# 06_PowerRele_OnOff.net
KiCad netlist of a schematic drawn in Altium Designer
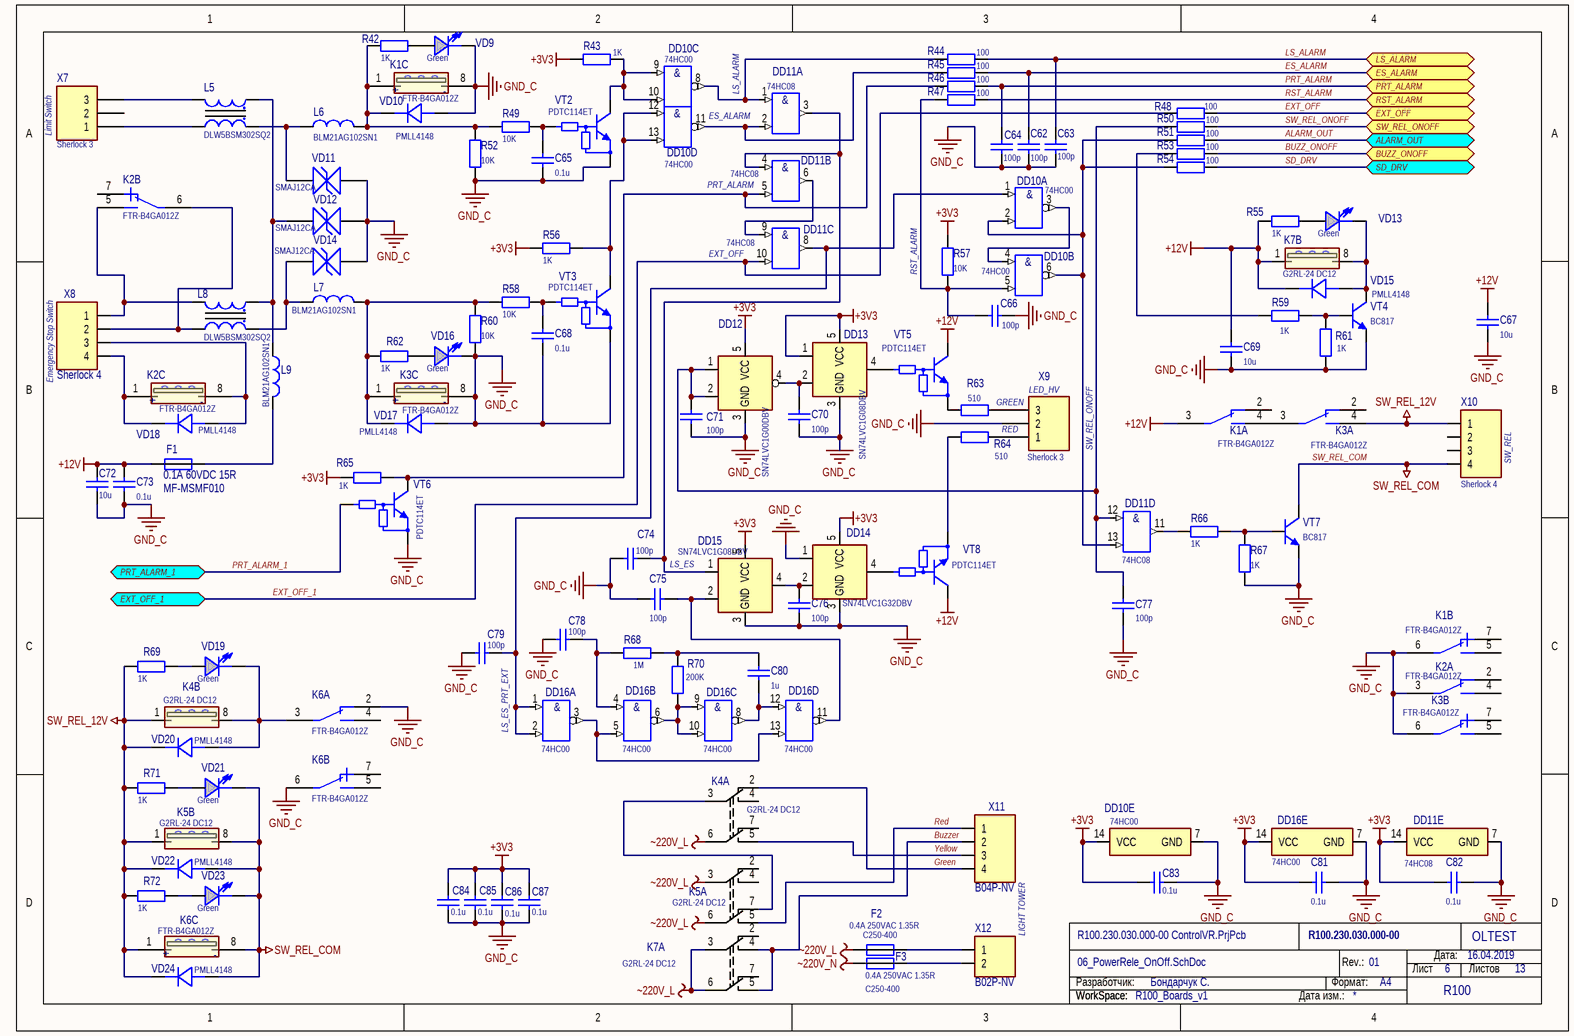
[diagram p0: 06_PowerRele_OnOff.SchDoc]

(export (version "E")
  (design (tool "Eeschema 10.0.6"))
  (components
    (comp (ref "C62")
      (value "100p")
      (footprint "mainLib:SMD_C_0603")
      (description "SMD C 0603 MURATA 100V 5% NP0")
      (fields (field (name "PARTNUMBER") "GRM1885C2A101JA01") (field (name "MANUFACTURER") "MURATA"))
      (libsource (lib "mainRCLib") (part "C0603 100p 100V 5%"))
    )
    (comp (ref "C63")
      (value "100p")
      (footprint "mainLib:SMD_C_0603")
      (description "SMD C 0603 MURATA 100V 5% NP0")
      (fields (field (name "PARTNUMBER") "GRM1885C2A101JA01") (field (name "MANUFACTURER") "MURATA"))
      (libsource (lib "mainRCLib") (part "C0603 100p 100V 5%"))
    )
    (comp (ref "C64")
      (value "100p")
      (footprint "mainLib:SMD_C_0603")
      (description "SMD C 0603 MURATA 100V 5% NP0")
      (fields (field (name "PARTNUMBER") "GRM1885C2A101JA01") (field (name "MANUFACTURER") "MURATA"))
      (libsource (lib "mainRCLib") (part "C0603 100p 100V 5%"))
    )
    (comp (ref "C65")
      (value "0.1u")
      (footprint "mainLib:SMD_C_0603")
      (description "SMD C 0603 MURATA 50V 10% X7R")
      (fields (field (name "PARTNUMBER") "GRM188R71H104K") (field (name "MANUFACTURER") "MURATA"))
      (libsource (lib "mainRCLib") (part "C0603 0.1u 50V 10%"))
    )
    (comp (ref "C66")
      (value "100p")
      (footprint "mainLib:SMD_C_0603")
      (description "SMD C 0603 MURATA 100V 5% NP0")
      (fields (field (name "PARTNUMBER") "GRM1885C2A101JA01") (field (name "MANUFACTURER") "MURATA"))
      (libsource (lib "mainRCLib") (part "C0603 100p 100V 5%"))
    )
    (comp (ref "C67")
      (value "10u")
      (footprint "mainLib:SMD_C_1206")
      (description "SMD C 1206 MURATA 25V 20% X5R")
      (fields (field (name "PARTNUMBER") "GRM31MR61E106M") (field (name "MANUFACTURER") "MURATA"))
      (libsource (lib "mainRCLib") (part "C1206 10u 25V 20%"))
    )
    (comp (ref "C68")
      (value "0.1u")
      (footprint "mainLib:SMD_C_0603")
      (description "SMD C 0603 MURATA 50V 10% X7R")
      (fields (field (name "PARTNUMBER") "GRM188R71H104K") (field (name "MANUFACTURER") "MURATA"))
      (libsource (lib "mainRCLib") (part "C0603 0.1u 50V 10%"))
    )
    (comp (ref "C69")
      (value "10u")
      (footprint "mainLib:SMD_C_1206")
      (description "SMD C 1206 MURATA 25V 20% X5R")
      (fields (field (name "PARTNUMBER") "GRM31MR61E106M") (field (name "MANUFACTURER") "MURATA"))
      (libsource (lib "mainRCLib") (part "C1206 10u 25V 20%"))
    )
    (comp (ref "C70")
      (value "100p")
      (footprint "mainLib:SMD_C_0603")
      (description "SMD C 0603 MURATA 100V 5% NP0")
      (fields (field (name "PARTNUMBER") "GRM1885C2A101JA01") (field (name "MANUFACTURER") "MURATA"))
      (libsource (lib "mainRCLib") (part "C0603 100p 100V 5%"))
    )
    (comp (ref "C71")
      (value "100p")
      (footprint "mainLib:SMD_C_0603")
      (description "SMD C 0603 MURATA 100V 5% NP0")
      (fields (field (name "PARTNUMBER") "GRM1885C2A101JA01") (field (name "MANUFACTURER") "MURATA"))
      (libsource (lib "mainRCLib") (part "C0603 100p 100V 5%"))
    )
    (comp (ref "C72")
      (value "10u")
      (footprint "mainLib:SMD_C_1206")
      (description "SMD C 1206 MURATA 25V 20% X5R")
      (fields (field (name "PARTNUMBER") "GRM31MR61E106M") (field (name "MANUFACTURER") "MURATA"))
      (libsource (lib "mainRCLib") (part "C1206 10u 25V 20%"))
    )
    (comp (ref "C73")
      (value "0.1u")
      (footprint "mainLib:SMD_C_0603")
      (description "SMD C 0603 MURATA 50V 10% X7R")
      (fields (field (name "PARTNUMBER") "GRM188R71H104K") (field (name "MANUFACTURER") "MURATA"))
      (libsource (lib "mainRCLib") (part "C0603 0.1u 50V 10%"))
    )
    (comp (ref "C74")
      (value "100p")
      (footprint "mainLib:SMD_C_0603")
      (description "SMD C 0603 MURATA 100V 5% NP0")
      (fields (field (name "PARTNUMBER") "GRM1885C2A101JA01") (field (name "MANUFACTURER") "MURATA"))
      (libsource (lib "mainRCLib") (part "C0603 100p 100V 5%"))
    )
    (comp (ref "C75")
      (value "100p")
      (footprint "mainLib:SMD_C_0603")
      (description "SMD C 0603 MURATA 100V 5% NP0")
      (fields (field (name "PARTNUMBER") "GRM1885C2A101JA01") (field (name "MANUFACTURER") "MURATA"))
      (libsource (lib "mainRCLib") (part "C0603 100p 100V 5%"))
    )
    (comp (ref "C76")
      (value "100p")
      (footprint "mainLib:SMD_C_0603")
      (description "SMD C 0603 MURATA 100V 5% NP0")
      (fields (field (name "PARTNUMBER") "GRM1885C2A101JA01") (field (name "MANUFACTURER") "MURATA"))
      (libsource (lib "mainRCLib") (part "C0603 100p 100V 5%"))
    )
    (comp (ref "C77")
      (value "100p")
      (footprint "mainLib:SMD_C_0603")
      (description "SMD C 0603 MURATA 100V 5% NP0")
      (fields (field (name "PARTNUMBER") "GRM1885C2A101JA01") (field (name "MANUFACTURER") "MURATA"))
      (libsource (lib "mainRCLib") (part "C0603 100p 100V 5%"))
    )
    (comp (ref "C78")
      (value "100p")
      (footprint "mainLib:SMD_C_0603")
      (description "SMD C 0603 MURATA 100V 5% NP0")
      (fields (field (name "PARTNUMBER") "GRM1885C2A101JA01") (field (name "MANUFACTURER") "MURATA"))
      (libsource (lib "mainRCLib") (part "C0603 100p 100V 5%"))
    )
    (comp (ref "C79")
      (value "100p")
      (footprint "mainLib:SMD_C_0603")
      (description "SMD C 0603 MURATA 100V 5% NP0")
      (fields (field (name "PARTNUMBER") "GRM1885C2A101JA01") (field (name "MANUFACTURER") "MURATA"))
      (libsource (lib "mainRCLib") (part "C0603 100p 100V 5%"))
    )
    (comp (ref "C80")
      (value "1u")
      (footprint "mainLib:SMD_C_0603")
      (description "SMD C 0603 MURATA 25V 10% X7R")
      (fields (field (name "PARTNUMBER") "GRM188R71E105KA12") (field (name "MANUFACTURER") "MURATA"))
      (libsource (lib "mainRCLib") (part "C0603 1uF 25V 10%"))
    )
    (comp (ref "C81")
      (value "0.1u")
      (footprint "mainLib:SMD_C_0603")
      (description "SMD C 0603 MURATA 50V 10% X7R")
      (fields (field (name "PARTNUMBER") "GRM188R71H104K") (field (name "MANUFACTURER") "MURATA"))
      (libsource (lib "mainRCLib") (part "C0603 0.1u 50V 10%"))
    )
    (comp (ref "C82")
      (value "0.1u")
      (footprint "mainLib:SMD_C_0603")
      (description "SMD C 0603 MURATA 50V 10% X7R")
      (fields (field (name "PARTNUMBER") "GRM188R71H104K") (field (name "MANUFACTURER") "MURATA"))
      (libsource (lib "mainRCLib") (part "C0603 0.1u 50V 10%"))
    )
    (comp (ref "C83")
      (value "0.1u")
      (footprint "mainLib:SMD_C_0603")
      (description "SMD C 0603 MURATA 50V 10% X7R")
      (fields (field (name "PARTNUMBER") "GRM188R71H104K") (field (name "MANUFACTURER") "MURATA"))
      (libsource (lib "mainRCLib") (part "C0603 0.1u 50V 10%"))
    )
    (comp (ref "C84")
      (value "0.1u")
      (footprint "mainLib:SMD_C_0603")
      (description "SMD C 0603 MURATA 50V 10% X7R")
      (fields (field (name "PARTNUMBER") "GRM188R71H104K") (field (name "MANUFACTURER") "MURATA"))
      (libsource (lib "mainRCLib") (part "C0603 0.1u 50V 10%"))
    )
    (comp (ref "C85")
      (value "0.1u")
      (footprint "mainLib:SMD_C_0603")
      (description "SMD C 0603 MURATA 50V 10% X7R")
      (fields (field (name "PARTNUMBER") "GRM188R71H104K") (field (name "MANUFACTURER") "MURATA"))
      (libsource (lib "mainRCLib") (part "C0603 0.1u 50V 10%"))
    )
    (comp (ref "C86")
      (value "0.1u")
      (footprint "mainLib:SMD_C_0603")
      (description "SMD C 0603 MURATA 50V 10% X7R")
      (fields (field (name "PARTNUMBER") "GRM188R71H104K") (field (name "MANUFACTURER") "MURATA"))
      (libsource (lib "mainRCLib") (part "C0603 0.1u 50V 10%"))
    )
    (comp (ref "C87")
      (value "0.1u")
      (footprint "mainLib:SMD_C_0603")
      (description "SMD C 0603 MURATA 50V 10% X7R")
      (fields (field (name "PARTNUMBER") "GRM188R71H104K") (field (name "MANUFACTURER") "MURATA"))
      (libsource (lib "mainRCLib") (part "C0603 0.1u 50V 10%"))
    )
    (comp (ref "DD10")
      (value "74HC00")
      (footprint "mainLib:TSSOP14")
      (description "Quad 2-Input Positive-NAND Gates, PW0014A")
      (fields
        (field (name "GENERIC PART NUMBER") "SN74HC00")
        (field (name "MANUFACTURER") "Texas Instruments")
      )
      (libsource (lib "mainLib") (part "74HC00"))
    )
    (comp (ref "DD11")
      (value "74HC08")
      (footprint "mainLib:TSSOP14")
      (description "Quad 2-Input Positive-NAND Gates, PW0014A")
      (fields
        (field (name "GENERIC PART NUMBER") "SN74HC00")
        (field (name "MANUFACTURER") "Texas Instruments")
      )
      (libsource (lib "mainLib") (part "74HC08"))
    )
    (comp (ref "DD12")
      (value "SN74LVC1G00DBV")
      (footprint "mainLib:SOT-23(DBV)")
      (description "2-in NAND")
      (fields (field (name "MANUFACTURER") "Texas Instruments"))
      (libsource (lib "mainLib") (part "SN74LVC1G00DBV"))
    )
    (comp (ref "DD13")
      (value "SN74LVC1G08DBV")
      (footprint "mainLib:SOT-23(DBV)")
      (description "2-in AND")
      (fields (field (name "MANUFACTURER") "Texas Instruments"))
      (libsource (lib "mainLib") (part "SN74LVC1G08DBV"))
    )
    (comp (ref "DD14")
      (value "SN74LVC1G32DBV")
      (footprint "mainLib:SOT-23(DBV)")
      (description "2-in OR")
      (fields (field (name "MANUFACTURER") "Texas Instruments"))
      (libsource (lib "mainLib") (part "SN74LVC1G32DBV"))
    )
    (comp (ref "DD15")
      (value "SN74LVC1G08DBV")
      (footprint "mainLib:SOT-23(DBV)")
      (description "2-in AND")
      (fields (field (name "MANUFACTURER") "Texas Instruments"))
      (libsource (lib "mainLib") (part "SN74LVC1G08DBV"))
    )
    (comp (ref "DD16")
      (value "74HC00")
      (footprint "mainLib:TSSOP14")
      (description "Quad 2-Input Positive-NAND Gates, PW0014A")
      (fields
        (field (name "GENERIC PART NUMBER") "SN74HC00")
        (field (name "MANUFACTURER") "Texas Instruments")
      )
      (libsource (lib "mainLib") (part "74HC00"))
    )
    (comp (ref "F1")
      (value "0.1A 60VDC 15R")
      (footprint "mainLib:MF-MSMF010")
      (description "PTC Resettable Fusses 0.1A 60VDC 15R")
      (fields (field (name "MANUFACTURER") "BOURNS") (field (name "PARTNUMBER") "MF-MSMF010"))
      (libsource (lib "mainLib") (part "MF-MSMF010 (0.1A 60VDC 15R)"))
    )
    (comp (ref "F2")
      (value "0.4A 250VAC 1.35R")
      (footprint "mainLib:C250-400")
      (description "PTC Resettable Fusses 0.4A 250VAC 1.35R")
      (fields
        (field (name "MANUFACTURER") "SEA&LAND ELECTRONIC CORP.")
        (field (name "PARTNUMBER") "C250-400")
      )
      (libsource (lib "mainLib") (part "C250-400 (0.4A 250VAC 1.35R)"))
    )
    (comp (ref "F3")
      (value "0.4A 250VAC 1.35R")
      (footprint "mainLib:C250-400")
      (description "PTC Resettable Fusses 0.4A 250VAC 1.35R")
      (fields
        (field (name "MANUFACTURER") "SEA&LAND ELECTRONIC CORP.")
        (field (name "PARTNUMBER") "C250-400")
      )
      (libsource (lib "mainLib") (part "C250-400 (0.4A 250VAC 1.35R)"))
    )
    (comp (ref "K1")
      (value "FTR-B4GA012Z")
      (footprint "mainLib:FTR-B4GA")
      (description "250VAC 1A DPDT 12VDC")
      (fields (field (name "MANUFACTURER") "Fujitsu"))
      (libsource (lib "mainLib") (part "FTR-B4GA012Z"))
    )
    (comp (ref "K2")
      (value "FTR-B4GA012Z")
      (footprint "mainLib:FTR-B4GA")
      (description "250VAC 1A DPDT 12VDC")
      (fields (field (name "MANUFACTURER") "Fujitsu"))
      (libsource (lib "") (part "FTR-B4GA012Z_1"))
    )
    (comp (ref "K3")
      (value "FTR-B4GA012Z")
      (footprint "mainLib:FTR-B4GA")
      (description "250VAC 1A DPDT 12VDC")
      (fields (field (name "MANUFACTURER") "Fujitsu"))
      (libsource (lib "mainLib") (part "FTR-B4GA012Z"))
    )
    (comp (ref "K4")
      (value "G2RL-24 DC12")
      (footprint "mainLib:G2RL")
      (description "440VAC 8A DPDT 12VDC")
      (fields (field (name "MANUFACTURER") "Omron"))
      (libsource (lib "mainLib") (part "G2RL-24 DC12"))
    )
    (comp (ref "K5")
      (value "G2RL-24 DC12")
      (footprint "mainLib:G2RL")
      (description "440VAC 8A DPDT 12VDC")
      (fields (field (name "MANUFACTURER") "Omron"))
      (libsource (lib "") (part "G2RL-24 DC12_1"))
    )
    (comp (ref "K6")
      (value "FTR-B4GA012Z")
      (footprint "mainLib:FTR-B4GA")
      (description "250VAC 1A DPDT 12VDC")
      (fields (field (name "MANUFACTURER") "Fujitsu"))
      (libsource (lib "mainLib") (part "FTR-B4GA012Z"))
    )
    (comp (ref "K7")
      (value "G2RL-24 DC12")
      (footprint "mainLib:G2RL")
      (description "440VAC 8A DPDT 12VDC")
      (fields (field (name "MANUFACTURER") "Omron"))
      (libsource (lib "mainLib") (part "G2RL-24 DC12"))
    )
    (comp (ref "L5")
      (value "DLW5BSM302SQ2")
      (footprint "mainLib:DLW5BS(AH)")
      (description "SMD Common Mode Choke Coil 0.5A Z = 3000 Ohm / 100 MHz")
      (fields (field (name "MANUFACTURER") "MURATA"))
      (libsource (lib "") (part "DLW5BSM302SQ2_1"))
    )
    (comp (ref "L6")
      (value "BLM21AG102SN1")
      (footprint "mainLib:SMD_L_L2_W1.25")
      (description "1000R 0.6A (100MHz)")
      (fields (field (name "MANUFACTURER") "TDK"))
      (libsource (lib "mainLib") (part "BLM21AG102SN1"))
    )
    (comp (ref "L7")
      (value "BLM21AG102SN1")
      (footprint "mainLib:SMD_L_L2_W1.25")
      (description "1000R 0.6A (100MHz)")
      (fields (field (name "MANUFACTURER") "TDK"))
      (libsource (lib "mainLib") (part "BLM21AG102SN1"))
    )
    (comp (ref "L8")
      (value "DLW5BSM302SQ2")
      (footprint "mainLib:DLW5BS(AH)")
      (description "SMD Common Mode Choke Coil 0.5A Z = 3000 Ohm / 100 MHz")
      (fields (field (name "MANUFACTURER") "MURATA"))
      (libsource (lib "mainLib") (part "DLW5BSM302SQ2"))
    )
    (comp (ref "L9")
      (value "BLM21AG102SN1")
      (footprint "mainLib:SMD_L_L2_W1.25")
      (description "1000R 0.6A (100MHz)")
      (fields (field (name "MANUFACTURER") "TDK"))
      (libsource (lib "mainLib") (part "BLM21AG102SN1"))
    )
    (comp (ref "R42")
      (value "1K")
      (footprint "mainLib:SMD_R_1206")
      (description "SMD R 1206 VISHAY 0.25W 200V 1% 100ppm")
      (fields (field (name "PARTNUMBER") "CRCW12061K00FK") (field (name "MANUFACTURER") "VISHAY"))
      (libsource (lib "mainRCLib") (part "R1206 1K 1%"))
    )
    (comp (ref "R43")
      (value "1K")
      (footprint "mainLib:SMD_R_0603")
      (description "SMD R 0603 VISHAY 0.1W 75V 1% 100ppm")
      (fields (field (name "PARTNUMBER") "CRCW06031K00FK") (field (name "MANUFACTURER") "VISHAY"))
      (libsource (lib "mainRCLib") (part "R0603 1K 1%"))
    )
    (comp (ref "R44")
      (value "100")
      (footprint "SMD_R_0603")
      (description "SMD R 0603 VISHAY 0.1W 75V 1% 100ppm")
      (fields (field (name "PARTNUMBER") "CRCW0603100RFK") (field (name "MANUFACTURER") "VISHAY"))
      (libsource (lib "mainRCLib") (part "R0603 100 1%"))
    )
    (comp (ref "R45")
      (value "100")
      (footprint "SMD_R_0603")
      (description "SMD R 0603 VISHAY 0.1W 75V 1% 100ppm")
      (fields (field (name "PARTNUMBER") "CRCW0603100RFK") (field (name "MANUFACTURER") "VISHAY"))
      (libsource (lib "mainRCLib") (part "R0603 100 1%"))
    )
    (comp (ref "R46")
      (value "100")
      (footprint "SMD_R_0603")
      (description "SMD R 0603 VISHAY 0.1W 75V 1% 100ppm")
      (fields (field (name "PARTNUMBER") "CRCW0603100RFK") (field (name "MANUFACTURER") "VISHAY"))
      (libsource (lib "mainRCLib") (part "R0603 100 1%"))
    )
    (comp (ref "R47")
      (value "100")
      (footprint "SMD_R_0603")
      (description "SMD R 0603 VISHAY 0.1W 75V 1% 100ppm")
      (fields (field (name "PARTNUMBER") "CRCW0603100RFK") (field (name "MANUFACTURER") "VISHAY"))
      (libsource (lib "mainRCLib") (part "R0603 100 1%"))
    )
    (comp (ref "R48")
      (value "100")
      (footprint "SMD_R_0603")
      (description "SMD R 0603 VISHAY 0.1W 75V 1% 100ppm")
      (fields (field (name "PARTNUMBER") "CRCW0603100RFK") (field (name "MANUFACTURER") "VISHAY"))
      (libsource (lib "mainRCLib") (part "R0603 100 1%"))
    )
    (comp (ref "R49")
      (value "10K")
      (footprint "SMD_R_0603")
      (description "SMD R 0603 VISHAY 0.1W 75V 1% 100ppm")
      (fields (field (name "PARTNUMBER") "CRCW060310K0FK") (field (name "MANUFACTURER") "VISHAY"))
      (libsource (lib "mainRCLib") (part "R0603 10К 1%"))
    )
    (comp (ref "R50")
      (value "100")
      (footprint "SMD_R_0603")
      (description "SMD R 0603 VISHAY 0.1W 75V 1% 100ppm")
      (fields (field (name "PARTNUMBER") "CRCW0603100RFK") (field (name "MANUFACTURER") "VISHAY"))
      (libsource (lib "mainRCLib") (part "R0603 100 1%"))
    )
    (comp (ref "R51")
      (value "100")
      (footprint "SMD_R_0603")
      (description "SMD R 0603 VISHAY 0.1W 75V 1% 100ppm")
      (fields (field (name "PARTNUMBER") "CRCW0603100RFK") (field (name "MANUFACTURER") "VISHAY"))
      (libsource (lib "mainRCLib") (part "R0603 100 1%"))
    )
    (comp (ref "R52")
      (value "10K")
      (footprint "SMD_R_0603")
      (description "SMD R 0603 VISHAY 0.1W 75V 1% 100ppm")
      (fields (field (name "PARTNUMBER") "CRCW060310K0FK") (field (name "MANUFACTURER") "VISHAY"))
      (libsource (lib "") (part "R0603 10К 1%_1"))
    )
    (comp (ref "R53")
      (value "100")
      (footprint "SMD_R_0603")
      (description "SMD R 0603 VISHAY 0.1W 75V 1% 100ppm")
      (fields (field (name "PARTNUMBER") "CRCW0603100RFK") (field (name "MANUFACTURER") "VISHAY"))
      (libsource (lib "mainRCLib") (part "R0603 100 1%"))
    )
    (comp (ref "R54")
      (value "100")
      (footprint "SMD_R_0603")
      (description "SMD R 0603 VISHAY 0.1W 75V 1% 100ppm")
      (fields (field (name "PARTNUMBER") "CRCW0603100RFK") (field (name "MANUFACTURER") "VISHAY"))
      (libsource (lib "mainRCLib") (part "R0603 100 1%"))
    )
    (comp (ref "R55")
      (value "1K")
      (footprint "mainLib:SMD_R_1206")
      (description "SMD R 1206 VISHAY 0.25W 200V 1% 100ppm")
      (fields (field (name "PARTNUMBER") "CRCW12061K00FK") (field (name "MANUFACTURER") "VISHAY"))
      (libsource (lib "mainRCLib") (part "R1206 1K 1%"))
    )
    (comp (ref "R56")
      (value "1K")
      (footprint "mainLib:SMD_R_0603")
      (description "SMD R 0603 VISHAY 0.1W 75V 1% 100ppm")
      (fields (field (name "PARTNUMBER") "CRCW06031K00FK") (field (name "MANUFACTURER") "VISHAY"))
      (libsource (lib "mainRCLib") (part "R0603 1K 1%"))
    )
    (comp (ref "R57")
      (value "10K")
      (footprint "SMD_R_0603")
      (description "SMD R 0603 VISHAY 0.1W 75V 1% 100ppm")
      (fields (field (name "PARTNUMBER") "CRCW060310K0FK") (field (name "MANUFACTURER") "VISHAY"))
      (libsource (lib "") (part "R0603 10К 1%_2"))
    )
    (comp (ref "R58")
      (value "10K")
      (footprint "SMD_R_0603")
      (description "SMD R 0603 VISHAY 0.1W 75V 1% 100ppm")
      (fields (field (name "PARTNUMBER") "CRCW060310K0FK") (field (name "MANUFACTURER") "VISHAY"))
      (libsource (lib "mainRCLib") (part "R0603 10К 1%"))
    )
    (comp (ref "R59")
      (value "1K")
      (footprint "mainLib:SMD_R_0805")
      (description "SMD R 0805 VISHAY 0.125W 150V 1% 100ppm")
      (fields (field (name "PARTNUMBER") "CRCW08051K00FK") (field (name "MANUFACTURER") "VISHAY"))
      (libsource (lib "") (part "R0805 1K 1%_1"))
    )
    (comp (ref "R60")
      (value "10K")
      (footprint "SMD_R_0603")
      (description "SMD R 0603 VISHAY 0.1W 75V 1% 100ppm")
      (fields (field (name "PARTNUMBER") "CRCW060310K0FK") (field (name "MANUFACTURER") "VISHAY"))
      (libsource (lib "") (part "R0603 10К 1%_1"))
    )
    (comp (ref "R61")
      (value "1K")
      (footprint "mainLib:SMD_R_0805")
      (description "SMD R 0805 VISHAY 0.125W 150V 1% 100ppm")
      (fields (field (name "PARTNUMBER") "CRCW08051K00FK") (field (name "MANUFACTURER") "VISHAY"))
      (libsource (lib "mainRCLib") (part "R0805 1K 1%"))
    )
    (comp (ref "R62")
      (value "1K")
      (footprint "mainLib:SMD_R_1206")
      (description "SMD R 1206 VISHAY 0.25W 200V 1% 100ppm")
      (fields (field (name "PARTNUMBER") "CRCW12061K00FK") (field (name "MANUFACTURER") "VISHAY"))
      (libsource (lib "mainRCLib") (part "R1206 1K 1%"))
    )
    (comp (ref "R63")
      (value "510")
      (footprint "mainLib:SMD_R_1206")
      (description "SMD R 1206 VISHAY 0.25W 200V 1% 100ppm")
      (fields (field (name "PARTNUMBER") "CRCW1206510RFK") (field (name "MANUFACTURER") "VISHAY"))
      (libsource (lib "mainRCLib") (part "R1206 510 1%"))
    )
    (comp (ref "R64")
      (value "510")
      (footprint "mainLib:SMD_R_1206")
      (description "SMD R 1206 VISHAY 0.25W 200V 1% 100ppm")
      (fields (field (name "PARTNUMBER") "CRCW1206510RFK") (field (name "MANUFACTURER") "VISHAY"))
      (libsource (lib "mainRCLib") (part "R1206 510 1%"))
    )
    (comp (ref "R65")
      (value "1K")
      (footprint "mainLib:SMD_R_0603")
      (description "SMD R 0603 VISHAY 0.1W 75V 1% 100ppm")
      (fields (field (name "PARTNUMBER") "CRCW06031K00FK") (field (name "MANUFACTURER") "VISHAY"))
      (libsource (lib "mainRCLib") (part "R0603 1K 1%"))
    )
    (comp (ref "R66")
      (value "1K")
      (footprint "mainLib:SMD_R_0805")
      (description "SMD R 0805 VISHAY 0.125W 150V 1% 100ppm")
      (fields (field (name "PARTNUMBER") "CRCW08051K00FK") (field (name "MANUFACTURER") "VISHAY"))
      (libsource (lib "") (part "R0805 1K 1%_1"))
    )
    (comp (ref "R67")
      (value "1K")
      (footprint "mainLib:SMD_R_0805")
      (description "SMD R 0805 VISHAY 0.125W 150V 1% 100ppm")
      (fields (field (name "PARTNUMBER") "CRCW08051K00FK") (field (name "MANUFACTURER") "VISHAY"))
      (libsource (lib "mainRCLib") (part "R0805 1K 1%"))
    )
    (comp (ref "R68")
      (value "1M")
      (footprint "mainLib:SMD_R_0805")
      (description "SMD R 0805 VISHAY 0.125W 150V 1% 100ppm")
      (fields (field (name "PARTNUMBER") "CRCW08051M00FK") (field (name "MANUFACTURER") "VISHAY"))
      (libsource (lib "mainRCLib") (part "R0805 1M 1%"))
    )
    (comp (ref "R69")
      (value "1K")
      (footprint "mainLib:SMD_R_1206")
      (description "SMD R 1206 VISHAY 0.25W 200V 1% 100ppm")
      (fields (field (name "PARTNUMBER") "CRCW12061K00FK") (field (name "MANUFACTURER") "VISHAY"))
      (libsource (lib "mainRCLib") (part "R1206 1K 1%"))
    )
    (comp (ref "R70")
      (value "200K")
      (footprint "mainLib:SMD_R_0805")
      (description "SMD R 0805 VISHAY 0.125W 150V 1% 100ppm")
      (fields (field (name "PARTNUMBER") "CRCW0805200KFK") (field (name "MANUFACTURER") "VISHAY"))
      (libsource (lib "mainRCLib") (part "R0805 200K 1%"))
    )
    (comp (ref "R71")
      (value "1K")
      (footprint "mainLib:SMD_R_1206")
      (description "SMD R 1206 VISHAY 0.25W 200V 1% 100ppm")
      (fields (field (name "PARTNUMBER") "CRCW12061K00FK") (field (name "MANUFACTURER") "VISHAY"))
      (libsource (lib "mainRCLib") (part "R1206 1K 1%"))
    )
    (comp (ref "R72")
      (value "1K")
      (footprint "mainLib:SMD_R_1206")
      (description "SMD R 1206 VISHAY 0.25W 200V 1% 100ppm")
      (fields (field (name "PARTNUMBER") "CRCW12061K00FK") (field (name "MANUFACTURER") "VISHAY"))
      (libsource (lib "mainRCLib") (part "R1206 1K 1%"))
    )
    (comp (ref "VD9")
      (value "Green")
      (footprint "mainLib:SMD_LED_LL_Green")
      (description "LED Green SMD")
      (fields (field (name "PARTNUMBER") "LL-S172GC-2A") (field (name "MANUFACTURER") "Lucky Light"))
      (libsource (lib "mainLib") (part "LL-S172GC-2A"))
    )
    (comp (ref "VD10")
      (value "PMLL4148")
      (footprint "mainLib:SOD80C")
      (description "If=0.2A, Vf=1V Vrrm=100V Diode (SOD80C)")
      (fields (field (name "MANUFACTURER") "NXP Semiconductors"))
      (libsource (lib "mainLib") (part "PMLL4148"))
    )
    (comp (ref "VD11")
      (value "SMAJ12CA")
      (footprint "mainLib:DO-214AC noPolarity")
      (description "400W 12V  Transient Voltage Suppressor, Bidirectional")
      (fields (field (name "MANUFACTURER") "LITTELFUSE"))
      (libsource (lib "mainLib") (part "SMAJ12CA"))
    )
    (comp (ref "VD12")
      (value "SMAJ12CA")
      (footprint "mainLib:DO-214AC noPolarity")
      (description "400W 12V  Transient Voltage Suppressor, Bidirectional")
      (fields (field (name "MANUFACTURER") "LITTELFUSE"))
      (libsource (lib "mainLib") (part "SMAJ12CA"))
    )
    (comp (ref "VD13")
      (value "Green")
      (footprint "mainLib:SMD_LED_LL_Green")
      (description "LED Green SMD")
      (fields (field (name "PARTNUMBER") "LL-S172GC-2A") (field (name "MANUFACTURER") "Lucky Light"))
      (libsource (lib "mainLib") (part "LL-S172GC-2A"))
    )
    (comp (ref "VD14")
      (value "SMAJ12CA")
      (footprint "mainLib:DO-214AC noPolarity")
      (description "400W 12V  Transient Voltage Suppressor, Bidirectional")
      (fields (field (name "MANUFACTURER") "LITTELFUSE"))
      (libsource (lib "mainLib") (part "SMAJ12CA"))
    )
    (comp (ref "VD15")
      (value "PMLL4148")
      (footprint "mainLib:SOD80C")
      (description "If=0.2A, Vf=1V Vrrm=100V Diode (SOD80C)")
      (fields (field (name "MANUFACTURER") "NXP Semiconductors"))
      (libsource (lib "mainLib") (part "PMLL4148"))
    )
    (comp (ref "VD16")
      (value "Green")
      (footprint "mainLib:SMD_LED_LL_Green")
      (description "LED Green SMD")
      (fields (field (name "PARTNUMBER") "LL-S172GC-2A") (field (name "MANUFACTURER") "Lucky Light"))
      (libsource (lib "mainLib") (part "LL-S172GC-2A"))
    )
    (comp (ref "VD17")
      (value "PMLL4148")
      (footprint "mainLib:SOD80C")
      (description "If=0.2A, Vf=1V Vrrm=100V Diode (SOD80C)")
      (fields (field (name "MANUFACTURER") "NXP Semiconductors"))
      (libsource (lib "mainLib") (part "PMLL4148"))
    )
    (comp (ref "VD18")
      (value "PMLL4148")
      (footprint "mainLib:SOD80C")
      (description "If=0.2A, Vf=1V Vrrm=100V Diode (SOD80C)")
      (fields (field (name "MANUFACTURER") "NXP Semiconductors"))
      (libsource (lib "mainLib") (part "PMLL4148"))
    )
    (comp (ref "VD19")
      (value "Green")
      (footprint "mainLib:SMD_LED_LL_Green")
      (description "LED Green SMD")
      (fields (field (name "PARTNUMBER") "LL-S172GC-2A") (field (name "MANUFACTURER") "Lucky Light"))
      (libsource (lib "mainLib") (part "LL-S172GC-2A"))
    )
    (comp (ref "VD20")
      (value "PMLL4148")
      (footprint "mainLib:SOD80C")
      (description "If=0.2A, Vf=1V Vrrm=100V Diode (SOD80C)")
      (fields (field (name "MANUFACTURER") "NXP Semiconductors"))
      (libsource (lib "mainLib") (part "PMLL4148"))
    )
    (comp (ref "VD21")
      (value "Green")
      (footprint "mainLib:SMD_LED_LL_Green")
      (description "LED Green SMD")
      (fields (field (name "PARTNUMBER") "LL-S172GC-2A") (field (name "MANUFACTURER") "Lucky Light"))
      (libsource (lib "mainLib") (part "LL-S172GC-2A"))
    )
    (comp (ref "VD22")
      (value "PMLL4148")
      (footprint "mainLib:SOD80C")
      (description "If=0.2A, Vf=1V Vrrm=100V Diode (SOD80C)")
      (fields (field (name "MANUFACTURER") "NXP Semiconductors"))
      (libsource (lib "mainLib") (part "PMLL4148"))
    )
    (comp (ref "VD23")
      (value "Green")
      (footprint "mainLib:SMD_LED_LL_Green")
      (description "LED Green SMD")
      (fields (field (name "PARTNUMBER") "LL-S172GC-2A") (field (name "MANUFACTURER") "Lucky Light"))
      (libsource (lib "mainLib") (part "LL-S172GC-2A"))
    )
    (comp (ref "VD24")
      (value "PMLL4148")
      (footprint "mainLib:SOD80C")
      (description "If=0.2A, Vf=1V Vrrm=100V Diode (SOD80C)")
      (fields (field (name "MANUFACTURER") "NXP Semiconductors"))
      (libsource (lib "mainLib") (part "PMLL4148"))
    )
    (comp (ref "VT2")
      (value "PDTC114ET")
      (footprint "mainLib:SOT23-3")
      (description "Digital Transistor (BRT), R1=10 kOhm, R2=10 kOhm, NPN Transistor")
      (fields (field (name "MANUFACTURER") "On Semiconductor"))
      (libsource (lib "mainLib") (part "PDTC114ET"))
    )
    (comp (ref "VT3")
      (value "PDTC114ET")
      (footprint "mainLib:SOT23-3")
      (description "Digital Transistor (BRT), R1=10 kOhm, R2=10 kOhm, NPN Transistor")
      (fields (field (name "MANUFACTURER") "On Semiconductor"))
      (libsource (lib "mainLib") (part "PDTC114ET"))
    )
    (comp (ref "VT4")
      (value "BC817")
      (footprint "mainLib:SOT23-3")
      (description "NPN Silicon, 3-Pin SOT-23")
      (fields (field (name "MANUFACTURER") "NXP"))
      (libsource (lib "mainLib") (part "BC817"))
    )
    (comp (ref "VT5")
      (value "PDTC114ET")
      (footprint "mainLib:SOT23-3")
      (description "Digital Transistor (BRT), R1=10 kOhm, R2=10 kOhm, NPN Transistor")
      (fields (field (name "MANUFACTURER") "On Semiconductor"))
      (libsource (lib "mainLib") (part "PDTC114ET"))
    )
    (comp (ref "VT6")
      (value "PDTC114ET")
      (footprint "mainLib:SOT23-3")
      (description "Digital Transistor (BRT), R1=10 kOhm, R2=10 kOhm, NPN Transistor")
      (fields (field (name "MANUFACTURER") "On Semiconductor"))
      (libsource (lib "mainLib") (part "PDTC114ET"))
    )
    (comp (ref "VT7")
      (value "BC817")
      (footprint "mainLib:SOT23-3")
      (description "NPN Silicon, 3-Pin SOT-23")
      (fields (field (name "MANUFACTURER") "NXP"))
      (libsource (lib "mainLib") (part "BC817"))
    )
    (comp (ref "VT8")
      (value "PDTC114ET")
      (footprint "mainLib:SOT23-3")
      (description "Digital Transistor (BRT), R1=10 kOhm, R2=10 kOhm, NPN Transistor")
      (fields (field (name "MANUFACTURER") "On Semiconductor"))
      (libsource (lib "mainLib") (part "PDTC114ET"))
    )
    (comp (ref "X7")
      (value "Sherlock 3")
      (footprint "mainLib:35362-0350")
      (description "Sherlock 3 Top, 2A 125V 2mm")
      (fields (field (name "PARTNUMBER") "35362-0350") (field (name "MANUFACTURER") "MOLEX"))
      (libsource (lib "mainLib") (part "35362-0350"))
    )
    (comp (ref "X8")
      (value "Sherlock 4")
      (footprint "35362-0450")
      (description "Sherlock 4 Top, 2A 125V 2mm")
      (fields (field (name "PARTNUMBER") "35362-0450") (field (name "MANUFACTURER") "MOLEX"))
      (libsource (lib "") (part "35362-0450_1"))
    )
    (comp (ref "X9")
      (value "Sherlock 3")
      (footprint "mainLib:35362-0350")
      (description "Sherlock 3 Top, 2A 125V 2mm")
      (fields (field (name "PARTNUMBER") "35362-0350") (field (name "MANUFACTURER") "MOLEX"))
      (libsource (lib "") (part "35362-0350_1"))
    )
    (comp (ref "X10")
      (value "Sherlock 4")
      (footprint "35362-0450")
      (description "Sherlock 4 Top, 2A 125V 2mm")
      (fields (field (name "PARTNUMBER") "35362-0450") (field (name "MANUFACTURER") "MOLEX"))
      (libsource (lib "mainLib") (part "35362-0450"))
    )
    (comp (ref "X11")
      (value "B04P-NV")
      (footprint "mainLib:B04P-NV (power)")
      (description "NV 4 конт LS=5.0 10A 250V PCB")
      (fields (field (name "MANUFACTURER") "JST"))
      (libsource (lib "mainLib") (part "B04P-NV"))
    )
    (comp (ref "X12")
      (value "B02P-NV")
      (footprint "mainLib:B02P-NV")
      (description "NV 2 LS=5.0 10A 250V PCB")
      (fields (field (name "MANUFACTURER") "JST"))
      (libsource (lib "mainLib") (part "B02P-NV"))
    )
  )
  (nets
    (net (code "1") (name "+3V3") (class "Default")
      (node (ref "C81") (pin "1") (pinfunction "1_1") (pintype "passive"))
      (node (ref "C82") (pin "1") (pinfunction "1_1") (pintype "passive"))
      (node (ref "C83") (pin "1") (pinfunction "1_1") (pintype "passive"))
      (node (ref "C84") (pin "2") (pinfunction "2_2") (pintype "passive"))
      (node (ref "C85") (pin "2") (pinfunction "2_2") (pintype "passive"))
      (node (ref "C86") (pin "2") (pinfunction "2_2") (pintype "passive"))
      (node (ref "C87") (pin "2") (pinfunction "2_2") (pintype "passive"))
      (node (ref "DD10") (pin "14") (pinfunction "VCC_14") (pintype "power_in"))
      (node (ref "DD11") (pin "14") (pinfunction "VCC_14") (pintype "power_in"))
      (node (ref "DD12") (pin "5") (pinfunction "VCC_5") (pintype "passive"))
      (node (ref "DD13") (pin "1") (pintype "passive"))
      (node (ref "DD13") (pin "5") (pinfunction "VCC_5") (pintype "passive"))
      (node (ref "DD14") (pin "5") (pinfunction "VCC_5") (pintype "passive"))
      (node (ref "DD15") (pin "5") (pinfunction "VCC_5") (pintype "passive"))
      (node (ref "DD16") (pin "14") (pinfunction "VCC_14") (pintype "power_in"))
      (node (ref "R43") (pin "2") (pinfunction "2_2") (pintype "passive"))
      (node (ref "R56") (pin "2") (pinfunction "2_2") (pintype "passive"))
      (node (ref "R57") (pin "1") (pinfunction "1_1") (pintype "passive"))
      (node (ref "R65") (pin "2") (pinfunction "2_2") (pintype "passive"))
    )
    (net (code "2") (name "+12V") (class "Default")
      (node (ref "C67") (pin "2") (pinfunction "2_2") (pintype "passive"))
      (node (ref "C69") (pin "2") (pinfunction "2_2") (pintype "passive"))
      (node (ref "C72") (pin "2") (pinfunction "2_2") (pintype "passive"))
      (node (ref "C73") (pin "2") (pinfunction "2_2") (pintype "passive"))
      (node (ref "F1") (pin "1") (pinfunction "1_1") (pintype "passive"))
      (node (ref "K1") (pin "3") (pinfunction "3_3") (pintype "passive"))
      (node (ref "K7") (pin "1") (pinfunction "1_1") (pintype "passive"))
      (node (ref "R55") (pin "1") (pinfunction "1_1") (pintype "passive"))
      (node (ref "VD15") (pin "2") (pinfunction "CATHODE_2") (pintype "passive"))
      (node (ref "VT5") (pin "3") (pinfunction "C_3") (pintype "passive"))
      (node (ref "VT8") (pin "3") (pinfunction "C_3") (pintype "passive"))
    )
    (net (code "3") (name "/ALARM_OUT") (class "Default")
      (node (ref "R51") (pin "2") (pinfunction "2_2") (pintype "passive"))
    )
    (net (code "4") (name "/BUZZ_ONOFF") (class "Default")
      (node (ref "R53") (pin "2") (pinfunction "2_2") (pintype "passive"))
    )
    (net (code "5") (name "/Buzzer") (class "Default")
      (node (ref "K7") (pin "4") (pinfunction "4_4") (pintype "passive"))
      (node (ref "K7") (pin "5") (pinfunction "5_5") (pintype "passive"))
      (node (ref "X11") (pin "2") (pinfunction "2_2") (pintype "passive"))
    )
    (net (code "6") (name "/ES_ALARM") (class "Default")
      (node (ref "C62") (pin "2") (pinfunction "2_2") (pintype "passive"))
      (node (ref "R45") (pin "2") (pinfunction "2_2") (pintype "passive"))
    )
    (net (code "7") (name "/EXT_OFF") (class "Default")
      (node (ref "R48") (pin "2") (pinfunction "2_2") (pintype "passive"))
    )
    (net (code "8") (name "/EXT_OFF_1") (class "Default")
      (node (ref "DD11") (pin "10") (pinfunction "3B_10") (pintype "input"))
      (node (ref "R48") (pin "1") (pinfunction "1_1") (pintype "passive"))
    )
    (net (code "9") (name "/Green") (class "Default")
      (node (ref "K4") (pin "2") (pinfunction "2_2") (pintype "passive"))
      (node (ref "X11") (pin "4") (pinfunction "4_4") (pintype "passive"))
    )
    (net (code "10") (name "/LS_ALARM") (class "Default")
      (node (ref "C63") (pin "2") (pinfunction "2_2") (pintype "passive"))
      (node (ref "R44") (pin "2") (pinfunction "2_2") (pintype "passive"))
    )
    (net (code "11") (name "/PRT_ALARM") (class "Default")
      (node (ref "C64") (pin "2") (pinfunction "2_2") (pintype "passive"))
      (node (ref "R46") (pin "2") (pinfunction "2_2") (pintype "passive"))
    )
    (net (code "12") (name "/PRT_ALARM_1") (class "Default")
      (node (ref "VT6") (pin "1") (pinfunction "B_1") (pintype "passive"))
    )
    (net (code "13") (name "/RST_ALARM") (class "Default")
      (node (ref "R47") (pin "2") (pinfunction "2_2") (pintype "passive"))
    )
    (net (code "14") (name "/Red") (class "Default")
      (node (ref "K5") (pin "5") (pinfunction "5_5") (pintype "passive"))
      (node (ref "X11") (pin "1") (pinfunction "1_1") (pintype "passive"))
    )
    (net (code "15") (name "/SD_DRV") (class "Default")
      (node (ref "R54") (pin "2") (pinfunction "2_2") (pintype "passive"))
    )
    (net (code "16") (name "/SW_REL_ONOFF") (class "Default")
      (node (ref "R50") (pin "2") (pinfunction "2_2") (pintype "passive"))
    )
    (net (code "17") (name "/Yellow") (class "Default")
      (node (ref "K4") (pin "5") (pinfunction "5_5") (pintype "passive"))
      (node (ref "X11") (pin "3") (pinfunction "3_3") (pintype "passive"))
    )
    (net (code "18") (name "GND_C") (class "Default")
      (node (ref "C62") (pin "1") (pinfunction "1_1") (pintype "passive"))
      (node (ref "C63") (pin "1") (pinfunction "1_1") (pintype "passive"))
      (node (ref "C64") (pin "1") (pinfunction "1_1") (pintype "passive"))
      (node (ref "C65") (pin "1") (pinfunction "1_1") (pintype "passive"))
      (node (ref "C66") (pin "1") (pinfunction "1_1") (pintype "passive"))
      (node (ref "C67") (pin "1") (pinfunction "1_1") (pintype "passive"))
      (node (ref "C68") (pin "1") (pinfunction "1_1") (pintype "passive"))
      (node (ref "C69") (pin "1") (pinfunction "1_1") (pintype "passive"))
      (node (ref "C70") (pin "2") (pinfunction "2_2") (pintype "passive"))
      (node (ref "C71") (pin "1") (pinfunction "1_1") (pintype "passive"))
      (node (ref "C72") (pin "1") (pinfunction "1_1") (pintype "passive"))
      (node (ref "C73") (pin "1") (pinfunction "1_1") (pintype "passive"))
      (node (ref "C74") (pin "2") (pinfunction "2_2") (pintype "passive"))
      (node (ref "C75") (pin "2") (pinfunction "2_2") (pintype "passive"))
      (node (ref "C76") (pin "2") (pinfunction "2_2") (pintype "passive"))
      (node (ref "C77") (pin "2") (pinfunction "2_2") (pintype "passive"))
      (node (ref "C78") (pin "2") (pinfunction "2_2") (pintype "passive"))
      (node (ref "C79") (pin "2") (pinfunction "2_2") (pintype "passive"))
      (node (ref "C81") (pin "2") (pinfunction "2_2") (pintype "passive"))
      (node (ref "C82") (pin "2") (pinfunction "2_2") (pintype "passive"))
      (node (ref "C83") (pin "2") (pinfunction "2_2") (pintype "passive"))
      (node (ref "C84") (pin "1") (pinfunction "1_1") (pintype "passive"))
      (node (ref "C85") (pin "1") (pinfunction "1_1") (pintype "passive"))
      (node (ref "C86") (pin "1") (pinfunction "1_1") (pintype "passive"))
      (node (ref "C87") (pin "1") (pinfunction "1_1") (pintype "passive"))
      (node (ref "DD10") (pin "7") (pinfunction "GND_7") (pintype "power_in"))
      (node (ref "DD11") (pin "7") (pinfunction "GND_7") (pintype "power_in"))
      (node (ref "DD12") (pin "3") (pinfunction "GND_3") (pintype "passive"))
      (node (ref "DD13") (pin "3") (pinfunction "GND_3") (pintype "passive"))
      (node (ref "DD14") (pin "1") (pintype "passive"))
      (node (ref "DD14") (pin "3") (pinfunction "GND_3") (pintype "passive"))
      (node (ref "DD15") (pin "3") (pinfunction "GND_3") (pintype "passive"))
      (node (ref "DD16") (pin "7") (pinfunction "GND_7") (pintype "power_in"))
      (node (ref "K1") (pin "6") (pinfunction "6_6") (pintype "passive"))
      (node (ref "K1") (pin "8") (pinfunction "8_8") (pintype "passive"))
      (node (ref "K2") (pin "3") (pinfunction "3_3") (pintype "passive"))
      (node (ref "K3") (pin "6") (pinfunction "6_6") (pintype "passive"))
      (node (ref "K3") (pin "8") (pinfunction "8_8") (pintype "passive"))
      (node (ref "K6") (pin "2") (pinfunction "2_2") (pintype "passive"))
      (node (ref "K6") (pin "6") (pinfunction "6_6") (pintype "passive"))
      (node (ref "R52") (pin "1") (pinfunction "1_1") (pintype "passive"))
      (node (ref "R60") (pin "1") (pinfunction "1_1") (pintype "passive"))
      (node (ref "R61") (pin "1") (pinfunction "1_1") (pintype "passive"))
      (node (ref "R67") (pin "1") (pinfunction "1_1") (pintype "passive"))
      (node (ref "VD10") (pin "1") (pinfunction "ANODE_1") (pintype "passive"))
      (node (ref "VD11") (pin "2") (pinfunction "2_2") (pintype "passive"))
      (node (ref "VD12") (pin "2") (pinfunction "2_2") (pintype "passive"))
      (node (ref "VD14") (pin "2") (pinfunction "2_2") (pintype "passive"))
      (node (ref "VD16") (pin "2") (pinfunction "CATHODE_2") (pintype "passive"))
      (node (ref "VD17") (pin "1") (pinfunction "ANODE_1") (pintype "passive"))
      (node (ref "VD9") (pin "2") (pinfunction "CATHODE_2") (pintype "passive"))
      (node (ref "VT2") (pin "2") (pinfunction "E_2") (pintype "passive"))
      (node (ref "VT3") (pin "2") (pinfunction "E_2") (pintype "passive"))
      (node (ref "VT4") (pin "2") (pinfunction "E_2") (pintype "passive"))
      (node (ref "VT6") (pin "2") (pinfunction "E_2") (pintype "passive"))
      (node (ref "VT7") (pin "2") (pinfunction "E_2") (pintype "passive"))
      (node (ref "X9") (pin "2") (pinfunction "2_2") (pintype "passive"))
    )
    (net (code "19") (name "Net-(C70-Pad1)") (class "Default")
      (node (ref "C70") (pin "1") (pinfunction "1_1") (pintype "passive"))
      (node (ref "DD12") (pin "4") (pintype "passive"))
      (node (ref "DD13") (pin "2") (pintype "passive"))
    )
    (net (code "20") (name "Net-(C76-Pad1)") (class "Default")
      (node (ref "C76") (pin "1") (pinfunction "1_1") (pintype "passive"))
      (node (ref "DD14") (pin "2") (pintype "passive"))
      (node (ref "DD15") (pin "4") (pintype "passive"))
    )
    (net (code "21") (name "Net-(C80-Pad2)") (class "Default")
      (node (ref "C80") (pin "2") (pinfunction "2_2") (pintype "passive"))
      (node (ref "R68") (pin "2") (pinfunction "2_2") (pintype "passive"))
      (node (ref "R70") (pin "2") (pinfunction "2_2") (pintype "passive"))
    )
    (net (code "22") (name "Net-(DD10A-1A)") (class "Default")
      (node (ref "C79") (pin "1") (pinfunction "1_1") (pintype "passive"))
      (node (ref "DD10") (pin "1") (pinfunction "1A_1") (pintype "input"))
      (node (ref "DD11") (pin "8") (pinfunction "3Y_8") (pintype "output"))
      (node (ref "DD16") (pin "1") (pinfunction "1A_1") (pintype "input"))
      (node (ref "DD16") (pin "2") (pinfunction "1B_2") (pintype "input"))
    )
    (net (code "23") (name "Net-(DD10A-1B)") (class "Default")
      (node (ref "DD10") (pin "2") (pinfunction "1B_2") (pintype "input"))
      (node (ref "DD10") (pin "6") (pinfunction "2Y_6") (pintype "output"))
      (node (ref "DD11") (pin "13") (pinfunction "4B_13") (pintype "input"))
      (node (ref "R51") (pin "1") (pinfunction "1_1") (pintype "passive"))
      (node (ref "R54") (pin "1") (pinfunction "1_1") (pintype "passive"))
    )
    (net (code "24") (name "Net-(DD10A-1Y)") (class "Default")
      (node (ref "DD10") (pin "3") (pinfunction "1Y_3") (pintype "output"))
      (node (ref "DD10") (pin "4") (pinfunction "2A_4") (pintype "input"))
    )
    (net (code "25") (name "Net-(DD10B-2B)") (class "Default")
      (node (ref "C66") (pin "2") (pinfunction "2_2") (pintype "passive"))
      (node (ref "DD10") (pin "5") (pinfunction "2B_5") (pintype "input"))
      (node (ref "R47") (pin "1") (pinfunction "1_1") (pintype "passive"))
      (node (ref "R57") (pin "2") (pinfunction "2_2") (pintype "passive"))
    )
    (net (code "26") (name "Net-(DD10C-3A)") (class "Default")
      (node (ref "DD10") (pin "10") (pinfunction "3B_10") (pintype "input"))
      (node (ref "DD10") (pin "9") (pinfunction "3A_9") (pintype "input"))
      (node (ref "R43") (pin "1") (pinfunction "1_1") (pintype "passive"))
      (node (ref "VT2") (pin "3") (pinfunction "C_3") (pintype "passive"))
    )
    (net (code "27") (name "Net-(DD10C-3Y)") (class "Default")
      (node (ref "DD10") (pin "8") (pinfunction "3Y_8") (pintype "output"))
      (node (ref "DD11") (pin "1") (pinfunction "1A_1") (pintype "input"))
      (node (ref "R44") (pin "1") (pinfunction "1_1") (pintype "passive"))
    )
    (net (code "28") (name "Net-(DD10D-4A)") (class "Default")
      (node (ref "DD10") (pin "12") (pinfunction "4A_12") (pintype "input"))
      (node (ref "DD10") (pin "13") (pinfunction "4B_13") (pintype "input"))
      (node (ref "R56") (pin "1") (pinfunction "1_1") (pintype "passive"))
      (node (ref "VT3") (pin "3") (pinfunction "C_3") (pintype "passive"))
    )
    (net (code "29") (name "Net-(DD10D-4Y)") (class "Default")
      (node (ref "DD10") (pin "11") (pinfunction "4Y_11") (pintype "output"))
      (node (ref "DD11") (pin "2") (pinfunction "1B_2") (pintype "input"))
      (node (ref "R45") (pin "1") (pinfunction "1_1") (pintype "passive"))
    )
    (net (code "30") (name "Net-(DD11A-1Y)") (class "Default")
      (node (ref "C74") (pin "1") (pinfunction "1_1") (pintype "passive"))
      (node (ref "DD11") (pin "3") (pinfunction "1Y_3") (pintype "output"))
      (node (ref "DD11") (pin "4") (pinfunction "2A_4") (pintype "input"))
      (node (ref "DD15") (pin "1") (pintype "passive"))
    )
    (net (code "31") (name "Net-(DD11B-2B)") (class "Default")
      (node (ref "DD11") (pin "5") (pinfunction "2B_5") (pintype "input"))
      (node (ref "R46") (pin "1") (pinfunction "1_1") (pintype "passive"))
      (node (ref "R65") (pin "1") (pinfunction "1_1") (pintype "passive"))
      (node (ref "VT6") (pin "3") (pinfunction "C_3") (pintype "passive"))
    )
    (net (code "32") (name "Net-(DD11B-2Y)") (class "Default")
      (node (ref "DD11") (pin "6") (pinfunction "2Y_6") (pintype "output"))
      (node (ref "DD11") (pin "9") (pinfunction "3A_9") (pintype "input"))
    )
    (net (code "33") (name "Net-(DD11D-4A)") (class "Default")
      (node (ref "C71") (pin "2") (pinfunction "2_2") (pintype "passive"))
      (node (ref "C77") (pin "1") (pinfunction "1_1") (pintype "passive"))
      (node (ref "DD11") (pin "12") (pinfunction "4A_12") (pintype "input"))
      (node (ref "DD12") (pin "1") (pintype "passive"))
      (node (ref "DD12") (pin "2") (pintype "passive"))
      (node (ref "R50") (pin "1") (pinfunction "1_1") (pintype "passive"))
    )
    (net (code "34") (name "Net-(DD11D-4Y)") (class "Default")
      (node (ref "DD11") (pin "11") (pinfunction "4Y_11") (pintype "output"))
      (node (ref "R66") (pin "1") (pinfunction "1_1") (pintype "passive"))
    )
    (net (code "35") (name "Net-(DD16A-1Y)") (class "Default")
      (node (ref "DD16") (pin "13") (pinfunction "4B_13") (pintype "input"))
      (node (ref "DD16") (pin "3") (pinfunction "1Y_3") (pintype "output"))
      (node (ref "DD16") (pin "5") (pinfunction "2B_5") (pintype "input"))
    )
    (net (code "36") (name "Net-(DD16B-2A)") (class "Default")
      (node (ref "C78") (pin "1") (pinfunction "1_1") (pintype "passive"))
      (node (ref "DD16") (pin "4") (pinfunction "2A_4") (pintype "input"))
      (node (ref "R68") (pin "1") (pinfunction "1_1") (pintype "passive"))
    )
    (net (code "37") (name "Net-(DD16B-2Y)") (class "Default")
      (node (ref "DD16") (pin "10") (pinfunction "3B_10") (pintype "input"))
      (node (ref "DD16") (pin "6") (pinfunction "2Y_6") (pintype "output"))
      (node (ref "DD16") (pin "9") (pinfunction "3A_9") (pintype "input"))
      (node (ref "R70") (pin "1") (pinfunction "1_1") (pintype "passive"))
    )
    (net (code "38") (name "Net-(DD16C-3Y)") (class "Default")
      (node (ref "C80") (pin "1") (pinfunction "1_1") (pintype "passive"))
      (node (ref "DD16") (pin "12") (pinfunction "4A_12") (pintype "input"))
      (node (ref "DD16") (pin "8") (pinfunction "3Y_8") (pintype "output"))
    )
    (net (code "39") (name "Net-(DD16D-4Y)") (class "Default")
      (node (ref "C75") (pin "1") (pinfunction "1_1") (pintype "passive"))
      (node (ref "DD15") (pin "2") (pintype "passive"))
      (node (ref "DD16") (pin "11") (pinfunction "4Y_11") (pintype "output"))
    )
    (net (code "40") (name "Net-(F1-Pad2)") (class "Default")
      (node (ref "F1") (pin "2") (pinfunction "2_2") (pintype "passive"))
      (node (ref "L9") (pin "2") (pinfunction "2_2") (pintype "passive"))
    )
    (net (code "41") (name "Net-(F2-Pad2)") (class "Default")
      (node (ref "F2") (pin "2") (pinfunction "2_2") (pintype "passive"))
      (node (ref "X12") (pin "1") (pinfunction "1_1") (pintype "passive"))
    )
    (net (code "42") (name "Net-(F3-Pad2)") (class "Default")
      (node (ref "F3") (pin "2") (pinfunction "2_2") (pintype "passive"))
      (node (ref "X12") (pin "2") (pinfunction "2_2") (pintype "passive"))
    )
    (net (code "43") (name "Net-(K1-Pad4)") (class "Default")
      (node (ref "K1") (pin "4") (pinfunction "4_4") (pintype "passive"))
      (node (ref "K3") (pin "3") (pinfunction "3_3") (pintype "passive"))
    )
    (net (code "44") (name "Net-(K2-Pad5)") (class "Default")
      (node (ref "K2") (pin "5") (pinfunction "5_5") (pintype "passive"))
      (node (ref "L8") (pin "2") (pinfunction "2_2") (pintype "passive"))
      (node (ref "X8") (pin "1") (pinfunction "1_1") (pintype "passive"))
    )
    (net (code "45") (name "Net-(K2-Pad6)") (class "Default")
      (node (ref "K2") (pin "6") (pinfunction "6_6") (pintype "passive"))
      (node (ref "L8") (pin "3") (pinfunction "3_3") (pintype "passive"))
      (node (ref "X8") (pin "2") (pinfunction "2_2") (pintype "passive"))
    )
    (net (code "46") (name "Net-(K4-Pad3)") (class "Default")
      (node (ref "K4") (pin "3") (pinfunction "3_3") (pintype "passive"))
      (node (ref "K5") (pin "7") (pinfunction "7_7") (pintype "passive"))
    )
    (net (code "47") (name "Net-(L5-Pad1)") (class "Default")
      (node (ref "L5") (pin "1") (pinfunction "1_1") (pintype "passive"))
      (node (ref "L6") (pin "1") (pinfunction "1_1") (pintype "passive"))
      (node (ref "VD11") (pin "1") (pinfunction "1_1") (pintype "passive"))
    )
    (net (code "48") (name "Net-(L5-Pad2)") (class "Default")
      (node (ref "L5") (pin "2") (pinfunction "2_2") (pintype "passive"))
      (node (ref "X7") (pin "1") (pinfunction "1_1") (pintype "passive"))
    )
    (net (code "49") (name "Net-(L5-Pad3)") (class "Default")
      (node (ref "L5") (pin "3") (pinfunction "3_3") (pintype "passive"))
      (node (ref "X7") (pin "3") (pinfunction "3_3") (pintype "passive"))
    )
    (net (code "50") (name "Net-(L5-Pad4)") (class "Default")
      (node (ref "L5") (pin "4") (pinfunction "4_4") (pintype "passive"))
      (node (ref "L8") (pin "1") (pinfunction "1_1") (pintype "passive"))
      (node (ref "L9") (pin "1") (pinfunction "1_1") (pintype "passive"))
      (node (ref "VD12") (pin "1") (pinfunction "1_1") (pintype "passive"))
    )
    (net (code "51") (name "Net-(L7-Pad1)") (class "Default")
      (node (ref "L7") (pin "1") (pinfunction "1_1") (pintype "passive"))
      (node (ref "L8") (pin "4") (pinfunction "4_4") (pintype "passive"))
      (node (ref "VD14") (pin "1") (pinfunction "1_1") (pintype "passive"))
    )
    (net (code "52") (name "Net-(R53-Pad1)") (class "Default")
      (node (ref "R53") (pin "1") (pinfunction "1_1") (pintype "passive"))
      (node (ref "R59") (pin "1") (pinfunction "1_1") (pintype "passive"))
    )
    (net (code "53") (name "Net-(R63-Pad2)") (class "Default")
      (node (ref "R63") (pin "2") (pinfunction "2_2") (pintype "passive"))
      (node (ref "X9") (pin "3") (pinfunction "3_3") (pintype "passive"))
    )
    (net (code "54") (name "Net-(R64-Pad2)") (class "Default")
      (node (ref "R64") (pin "2") (pinfunction "2_2") (pintype "passive"))
      (node (ref "X9") (pin "1") (pinfunction "1_1") (pintype "passive"))
    )
    (net (code "55") (name "Net-(VD9-ANODE)") (class "Default")
      (node (ref "R42") (pin "2") (pinfunction "2_2") (pintype "passive"))
      (node (ref "VD9") (pin "1") (pinfunction "ANODE_1") (pintype "passive"))
    )
    (net (code "56") (name "Net-(VD10-CATHODE)") (class "Default")
      (node (ref "K1") (pin "1") (pinfunction "1_1") (pintype "passive"))
      (node (ref "L6") (pin "2") (pinfunction "2_2") (pintype "passive"))
      (node (ref "R42") (pin "1") (pinfunction "1_1") (pintype "passive"))
      (node (ref "R49") (pin "1") (pinfunction "1_1") (pintype "passive"))
      (node (ref "R52") (pin "2") (pinfunction "2_2") (pintype "passive"))
      (node (ref "VD10") (pin "2") (pinfunction "CATHODE_2") (pintype "passive"))
    )
    (net (code "57") (name "Net-(VD13-ANODE)") (class "Default")
      (node (ref "R55") (pin "2") (pinfunction "2_2") (pintype "passive"))
      (node (ref "VD13") (pin "1") (pinfunction "ANODE_1") (pintype "passive"))
    )
    (net (code "58") (name "Net-(VD13-CATHODE)") (class "Default")
      (node (ref "K7") (pin "8") (pinfunction "8_8") (pintype "passive"))
      (node (ref "VD13") (pin "2") (pinfunction "CATHODE_2") (pintype "passive"))
      (node (ref "VD15") (pin "1") (pinfunction "ANODE_1") (pintype "passive"))
      (node (ref "VT4") (pin "3") (pinfunction "C_3") (pintype "passive"))
    )
    (net (code "59") (name "Net-(VD16-ANODE)") (class "Default")
      (node (ref "R62") (pin "2") (pinfunction "2_2") (pintype "passive"))
      (node (ref "VD16") (pin "1") (pinfunction "ANODE_1") (pintype "passive"))
    )
    (net (code "60") (name "Net-(VD17-CATHODE)") (class "Default")
      (node (ref "K3") (pin "1") (pinfunction "1_1") (pintype "passive"))
      (node (ref "L7") (pin "2") (pinfunction "2_2") (pintype "passive"))
      (node (ref "R58") (pin "1") (pinfunction "1_1") (pintype "passive"))
      (node (ref "R60") (pin "2") (pinfunction "2_2") (pintype "passive"))
      (node (ref "R62") (pin "1") (pinfunction "1_1") (pintype "passive"))
      (node (ref "VD17") (pin "2") (pinfunction "CATHODE_2") (pintype "passive"))
    )
    (net (code "61") (name "Net-(VD18-ANODE)") (class "Default")
      (node (ref "K2") (pin "8") (pinfunction "8_8") (pintype "passive"))
      (node (ref "VD18") (pin "1") (pinfunction "ANODE_1") (pintype "passive"))
      (node (ref "X8") (pin "3") (pinfunction "3_3") (pintype "passive"))
    )
    (net (code "62") (name "Net-(VD18-CATHODE)") (class "Default")
      (node (ref "K2") (pin "1") (pinfunction "1_1") (pintype "passive"))
      (node (ref "VD18") (pin "2") (pinfunction "CATHODE_2") (pintype "passive"))
      (node (ref "X8") (pin "4") (pinfunction "4_4") (pintype "passive"))
    )
    (net (code "63") (name "Net-(VD19-ANODE)") (class "Default")
      (node (ref "R69") (pin "2") (pinfunction "2_2") (pintype "passive"))
      (node (ref "VD19") (pin "1") (pinfunction "ANODE_1") (pintype "passive"))
    )
    (net (code "64") (name "Net-(VD19-CATHODE)") (class "Default")
      (node (ref "K4") (pin "8") (pinfunction "8_8") (pintype "passive"))
      (node (ref "K6") (pin "3") (pinfunction "3_3") (pintype "passive"))
      (node (ref "VD19") (pin "2") (pinfunction "CATHODE_2") (pintype "passive"))
      (node (ref "VD20") (pin "1") (pinfunction "ANODE_1") (pintype "passive"))
    )
    (net (code "65") (name "Net-(VD21-ANODE)") (class "Default")
      (node (ref "R71") (pin "2") (pinfunction "2_2") (pintype "passive"))
      (node (ref "VD21") (pin "1") (pinfunction "ANODE_1") (pintype "passive"))
    )
    (net (code "66") (name "Net-(VD23-ANODE)") (class "Default")
      (node (ref "R72") (pin "2") (pinfunction "2_2") (pintype "passive"))
      (node (ref "VD23") (pin "1") (pinfunction "ANODE_1") (pintype "passive"))
    )
    (net (code "67") (name "Net-(VT2-B)") (class "Default")
      (node (ref "C65") (pin "2") (pinfunction "2_2") (pintype "passive"))
      (node (ref "R49") (pin "2") (pinfunction "2_2") (pintype "passive"))
      (node (ref "VT2") (pin "1") (pinfunction "B_1") (pintype "passive"))
    )
    (net (code "68") (name "Net-(VT3-B)") (class "Default")
      (node (ref "C68") (pin "2") (pinfunction "2_2") (pintype "passive"))
      (node (ref "R58") (pin "2") (pinfunction "2_2") (pintype "passive"))
      (node (ref "VT3") (pin "1") (pinfunction "B_1") (pintype "passive"))
    )
    (net (code "69") (name "Net-(VT4-B)") (class "Default")
      (node (ref "R59") (pin "2") (pinfunction "2_2") (pintype "passive"))
      (node (ref "R61") (pin "2") (pinfunction "2_2") (pintype "passive"))
      (node (ref "VT4") (pin "1") (pinfunction "B_1") (pintype "passive"))
    )
    (net (code "70") (name "Net-(VT5-B)") (class "Default")
      (node (ref "DD13") (pin "4") (pintype "passive"))
      (node (ref "VT5") (pin "1") (pinfunction "B_1") (pintype "passive"))
    )
    (net (code "71") (name "Net-(VT5-E)") (class "Default")
      (node (ref "R63") (pin "1") (pinfunction "1_1") (pintype "passive"))
      (node (ref "VT5") (pin "2") (pinfunction "E_2") (pintype "passive"))
    )
    (net (code "72") (name "Net-(VT7-B)") (class "Default")
      (node (ref "R66") (pin "2") (pinfunction "2_2") (pintype "passive"))
      (node (ref "R67") (pin "2") (pinfunction "2_2") (pintype "passive"))
      (node (ref "VT7") (pin "1") (pinfunction "B_1") (pintype "passive"))
    )
    (net (code "73") (name "Net-(VT8-B)") (class "Default")
      (node (ref "DD14") (pin "4") (pintype "passive"))
      (node (ref "VT8") (pin "1") (pinfunction "B_1") (pintype "passive"))
    )
    (net (code "74") (name "Net-(VT8-E)") (class "Default")
      (node (ref "R64") (pin "1") (pinfunction "1_1") (pintype "passive"))
      (node (ref "VT8") (pin "2") (pinfunction "E_2") (pintype "passive"))
    )
    (net (code "75") (name "SW_REL_12V") (class "Default")
      (node (ref "K3") (pin "4") (pinfunction "4_4") (pintype "passive"))
      (node (ref "K4") (pin "1") (pinfunction "1_1") (pintype "passive"))
      (node (ref "K5") (pin "1") (pinfunction "1_1") (pintype "passive"))
      (node (ref "K6") (pin "1") (pinfunction "1_1") (pintype "passive"))
      (node (ref "R69") (pin "1") (pinfunction "1_1") (pintype "passive"))
      (node (ref "R71") (pin "1") (pinfunction "1_1") (pintype "passive"))
      (node (ref "R72") (pin "1") (pinfunction "1_1") (pintype "passive"))
      (node (ref "VD20") (pin "2") (pinfunction "CATHODE_2") (pintype "passive"))
      (node (ref "VD22") (pin "2") (pinfunction "CATHODE_2") (pintype "passive"))
      (node (ref "VD24") (pin "2") (pinfunction "CATHODE_2") (pintype "passive"))
      (node (ref "X10") (pin "1") (pinfunction "1_1") (pintype "passive"))
    )
    (net (code "76") (name "SW_REL_COM") (class "Default")
      (node (ref "K5") (pin "8") (pinfunction "8_8") (pintype "passive"))
      (node (ref "K6") (pin "8") (pinfunction "8_8") (pintype "passive"))
      (node (ref "VD21") (pin "2") (pinfunction "CATHODE_2") (pintype "passive"))
      (node (ref "VD22") (pin "1") (pinfunction "ANODE_1") (pintype "passive"))
      (node (ref "VD23") (pin "2") (pinfunction "CATHODE_2") (pintype "passive"))
      (node (ref "VD24") (pin "1") (pinfunction "ANODE_1") (pintype "passive"))
      (node (ref "VT7") (pin "3") (pinfunction "C_3") (pintype "passive"))
      (node (ref "X10") (pin "4") (pinfunction "4_4") (pintype "passive"))
    )
    (net (code "77") (name "unconnected-(K1-Pad2)") (class "Default")
      (node (ref "K1") (pin "2") (pinfunction "2_2") (pintype "passive"))
    )
    (net (code "78") (name "unconnected-(K1-Pad5)") (class "Default")
      (node (ref "K1") (pin "5") (pinfunction "5_5") (pintype "passive"))
    )
    (net (code "79") (name "unconnected-(K1-Pad7)") (class "Default")
      (node (ref "K1") (pin "7") (pinfunction "7_7") (pintype "passive"))
    )
    (net (code "80") (name "unconnected-(K2-Pad2)") (class "Default")
      (node (ref "K2") (pin "2") (pinfunction "2_2") (pintype "passive"))
    )
    (net (code "81") (name "unconnected-(K2-Pad4)") (class "Default")
      (node (ref "K2") (pin "4") (pinfunction "4_4") (pintype "passive"))
    )
    (net (code "82") (name "unconnected-(K2-Pad7)") (class "Default")
      (node (ref "K2") (pin "7") (pinfunction "7_7") (pintype "passive"))
    )
    (net (code "83") (name "unconnected-(K3-Pad2)") (class "Default")
      (node (ref "K3") (pin "2") (pinfunction "2_2") (pintype "passive"))
    )
    (net (code "84") (name "unconnected-(K3-Pad5)") (class "Default")
      (node (ref "K3") (pin "5") (pinfunction "5_5") (pintype "passive"))
    )
    (net (code "85") (name "unconnected-(K3-Pad7)") (class "Default")
      (node (ref "K3") (pin "7") (pinfunction "7_7") (pintype "passive"))
    )
    (net (code "86") (name "unconnected-(K4-Pad4)") (class "Default")
      (node (ref "K4") (pin "4") (pinfunction "4_4") (pintype "passive"))
    )
    (net (code "87") (name "unconnected-(K4-Pad7)") (class "Default")
      (node (ref "K4") (pin "7") (pinfunction "7_7") (pintype "passive"))
    )
    (net (code "88") (name "unconnected-(K5-Pad2)") (class "Default")
      (node (ref "K5") (pin "2") (pinfunction "2_2") (pintype "passive"))
    )
    (net (code "89") (name "unconnected-(K5-Pad4)") (class "Default")
      (node (ref "K5") (pin "4") (pinfunction "4_4") (pintype "passive"))
    )
    (net (code "90") (name "unconnected-(K6-Pad4)") (class "Default")
      (node (ref "K6") (pin "4") (pinfunction "4_4") (pintype "passive"))
    )
    (net (code "91") (name "unconnected-(K6-Pad5)") (class "Default")
      (node (ref "K6") (pin "5") (pinfunction "5_5") (pintype "passive"))
    )
    (net (code "92") (name "unconnected-(K6-Pad7)") (class "Default")
      (node (ref "K6") (pin "7") (pinfunction "7_7") (pintype "passive"))
    )
    (net (code "93") (name "unconnected-(K7-Pad2)") (class "Default")
      (node (ref "K7") (pin "2") (pinfunction "2_2") (pintype "passive"))
    )
    (net (code "94") (name "unconnected-(K7-Pad7)") (class "Default")
      (node (ref "K7") (pin "7") (pinfunction "7_7") (pintype "passive"))
    )
    (net (code "95") (name "unconnected-(X7-Pad2)") (class "Default")
      (node (ref "X7") (pin "2") (pinfunction "2_2") (pintype "passive"))
    )
    (net (code "96") (name "unconnected-(X10-Pad2)") (class "Default")
      (node (ref "X10") (pin "2") (pinfunction "2_2") (pintype "passive"))
    )
    (net (code "97") (name "unconnected-(X10-Pad3)") (class "Default")
      (node (ref "X10") (pin "3") (pinfunction "3_3") (pintype "passive"))
    )
    (net (code "98") (name "~220V_L") (class "Default")
      (node (ref "F2") (pin "1") (pinfunction "1_1") (pintype "passive"))
      (node (ref "K4") (pin "6") (pinfunction "6_6") (pintype "passive"))
      (node (ref "K5") (pin "3") (pinfunction "3_3") (pintype "passive"))
      (node (ref "K5") (pin "6") (pinfunction "6_6") (pintype "passive"))
      (node (ref "K7") (pin "3") (pinfunction "3_3") (pintype "passive"))
      (node (ref "K7") (pin "6") (pinfunction "6_6") (pintype "passive"))
    )
    (net (code "99") (name "~220V_N") (class "Default")
      (node (ref "F3") (pin "1") (pinfunction "1_1") (pintype "passive"))
    )
  )
)
